# Lm234.net
KiCad netlist of a schematic drawn in Altium Designer
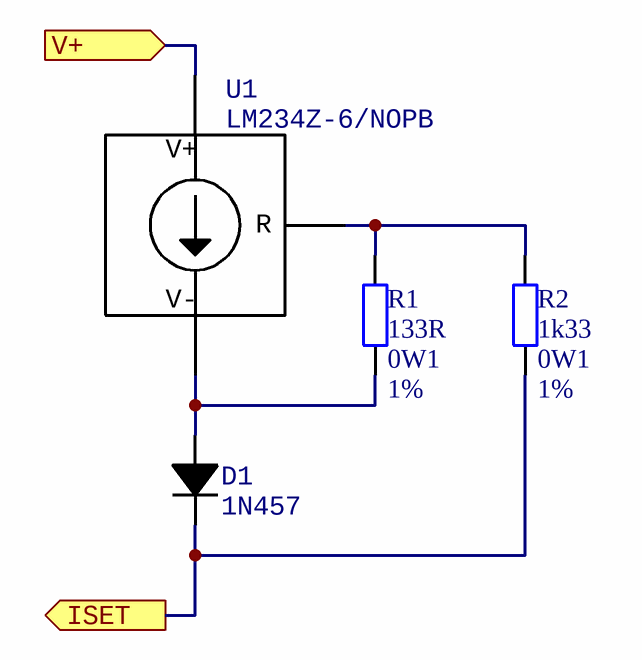
[diagram p0: Lm234.SchDoc]

(export (version "E")
  (design (tool "Eeschema 10.0.6"))
  (components
    (comp (ref "D1")
      (value "1N457")
      (footprint "DO-35")
      (description "Universal diode")
      (libsource (lib "semicon") (part "1N400X"))
    )
    (comp (ref "R1")
      (value "133R")
      (footprint "RESC1608N")
      (description "Resistor")
      (fields (field (name "POWER") "0W1") (field (name "TOLERANCE") "1%"))
      (libsource (lib "passives") (part "Resistor"))
    )
    (comp (ref "R2")
      (value "1k33")
      (footprint "RESC1608N")
      (description "Resistor")
      (fields (field (name "POWER") "0W1") (field (name "TOLERANCE") "1%"))
      (libsource (lib "passives") (part "Resistor"))
    )
    (comp (ref "U1")
      (value "LM234Z-6/NOPB")
      (footprint "TO92")
      (description "Three terminal adjustable current sources")
      (libsource (lib "power") (part "LM234Z-6/NOPB"))
    )
  )
  (nets
    (net (code "1") (name "/ISET") (class "Default")
      (node (ref "D1") (pin "1") (pinfunction "K_1") (pintype "passive"))
      (node (ref "R2") (pin "1") (pinfunction "1_1") (pintype "passive"))
    )
    (net (code "2") (name "/V+") (class "Default")
      (node (ref "U1") (pin "3") (pinfunction "V+_3") (pintype "passive"))
    )
    (net (code "3") (name "Net-(D1-A)") (class "Default")
      (node (ref "D1") (pin "2") (pinfunction "A_2") (pintype "passive"))
      (node (ref "R1") (pin "1") (pinfunction "1_1") (pintype "passive"))
      (node (ref "U1") (pin "1") (pinfunction "V-_1") (pintype "passive"))
    )
    (net (code "4") (name "Net-(U1-ADJ)") (class "Default")
      (node (ref "R1") (pin "2") (pinfunction "2_2") (pintype "passive"))
      (node (ref "R2") (pin "2") (pinfunction "2_2") (pintype "passive"))
      (node (ref "U1") (pin "2") (pinfunction "ADJ_2") (pintype "passive"))
    )
  )
)
